# led.net
KiCad netlist of a schematic drawn in Altium Designer
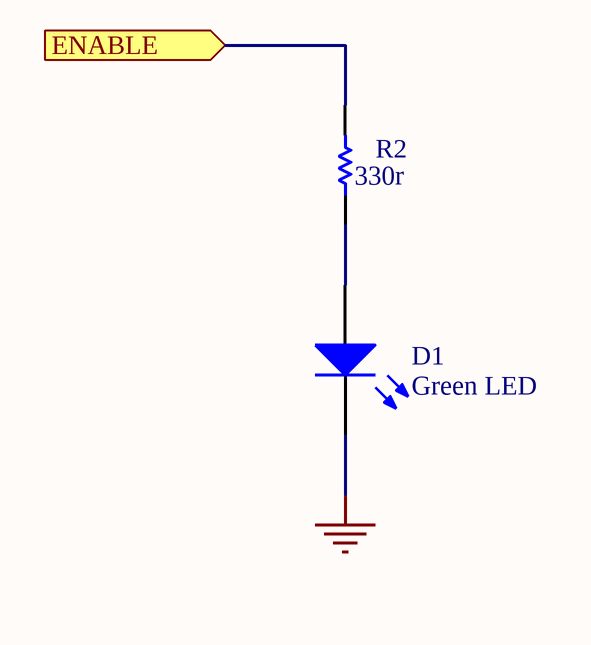
[diagram p0: led.SchDoc]

(export (version "E")
  (design (tool "Eeschema 10.0.6"))
  (components
    (comp (ref "D1")
      (value "Green LED")
      (footprint "LED 0805")
      (description "Typical INFRARED GaAs LED")
      (fields (field (name "PUBLISHER") "Altium Limited"))
      (libsource (lib "Miscellaneous Devices") (part "LED0"))
    )
    (comp (ref "R2")
      (value "330r")
      (footprint "RESC1608N")
      (description "Resistor")
      (fields (field (name "PUBLISHER") "Altium Limited"))
      (libsource (lib "Miscellaneous Devices") (part "Res1"))
    )
  )
  (nets
    (net (code "1") (name "/ENABLE") (class "Default")
      (node (ref "R2") (pin "2") (pinfunction "2_2") (pintype "passive"))
    )
    (net (code "2") (name "Gnd") (class "Default")
      (node (ref "D1") (pin "2") (pinfunction "K_2") (pintype "passive"))
    )
    (net (code "3") (name "Net-(D1-A)") (class "Default")
      (node (ref "D1") (pin "1") (pinfunction "A_1") (pintype "passive"))
      (node (ref "R2") (pin "1") (pinfunction "1_1") (pintype "passive"))
    )
  )
)
